# EV76C661_Sheet.net
KiCad netlist of a schematic drawn in Altium Designer
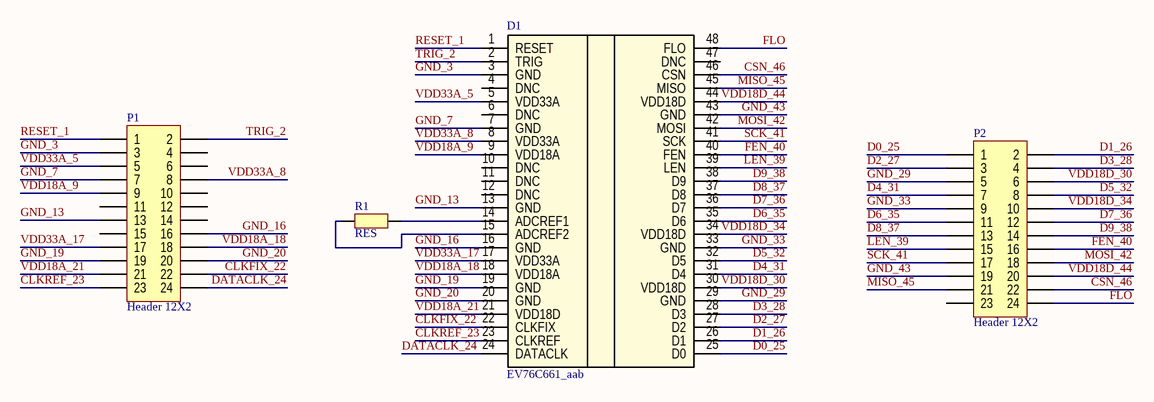
[diagram p0: EV76C661_Sheet.SchDoc]

(export (version "E")
  (design (tool "Eeschema 10.0.6"))
  (components
    (comp (ref "D1")
      (value "EV76C661_aab")
      (footprint "aab_Active:EV76C611_aab")
      (libsource (lib "aab_Schlib") (part "EV76C661_aab"))
    )
    (comp (ref "P1")
      (value "Header 12X2")
      (footprint "HDR2X12")
      (description "Header, 12-Pin, Dual row")
      (fields (field (name "PUBLISHER") "Altium Limited"))
      (libsource (lib "Miscellaneous Connectors") (part "Header 12X2"))
    )
    (comp (ref "P2")
      (value "Header 12X2")
      (footprint "HDR2X12")
      (description "Header, 12-Pin, Dual row")
      (fields (field (name "PUBLISHER") "Altium Limited"))
      (libsource (lib "Miscellaneous Connectors") (part "Header 12X2"))
    )
    (comp (ref "R1") (value "RES") (footprint "RES") (libsource (lib "aab_Schlib") (part "RES")))
  )
  (nets
    (net (code "1") (name "/CLKFIX_22") (class "Default")
      (node (ref "D1") (pin "22") (pinfunction "CLKFIX_22") (pintype "passive"))
      (node (ref "P1") (pin "22") (pinfunction "22_22") (pintype "passive"))
    )
    (net (code "2") (name "/CLKREF_23") (class "Default")
      (node (ref "D1") (pin "23") (pinfunction "CLKREF_23") (pintype "passive"))
      (node (ref "P1") (pin "23") (pinfunction "23_23") (pintype "passive"))
    )
    (net (code "3") (name "/CSN_46") (class "Default")
      (node (ref "D1") (pin "46") (pinfunction "CSN_46") (pintype "passive"))
      (node (ref "P2") (pin "22") (pinfunction "22_22") (pintype "passive"))
    )
    (net (code "4") (name "/D0_25") (class "Default")
      (node (ref "D1") (pin "25") (pinfunction "D0_25") (pintype "passive"))
      (node (ref "P2") (pin "1") (pinfunction "1_1") (pintype "passive"))
    )
    (net (code "5") (name "/D1_26") (class "Default")
      (node (ref "D1") (pin "26") (pinfunction "D1_26") (pintype "passive"))
      (node (ref "P2") (pin "2") (pinfunction "2_2") (pintype "passive"))
    )
    (net (code "6") (name "/D2_27") (class "Default")
      (node (ref "D1") (pin "27") (pinfunction "D2_27") (pintype "passive"))
      (node (ref "P2") (pin "3") (pinfunction "3_3") (pintype "passive"))
    )
    (net (code "7") (name "/D3_28") (class "Default")
      (node (ref "D1") (pin "28") (pinfunction "D3_28") (pintype "passive"))
      (node (ref "P2") (pin "4") (pinfunction "4_4") (pintype "passive"))
    )
    (net (code "8") (name "/D4_31") (class "Default")
      (node (ref "D1") (pin "31") (pinfunction "D4_31") (pintype "passive"))
      (node (ref "P2") (pin "7") (pinfunction "7_7") (pintype "passive"))
    )
    (net (code "9") (name "/D5_32") (class "Default")
      (node (ref "D1") (pin "32") (pinfunction "D5_32") (pintype "passive"))
      (node (ref "P2") (pin "8") (pinfunction "8_8") (pintype "passive"))
    )
    (net (code "10") (name "/D6_35") (class "Default")
      (node (ref "D1") (pin "35") (pinfunction "D6_35") (pintype "passive"))
      (node (ref "P2") (pin "11") (pinfunction "11_11") (pintype "passive"))
    )
    (net (code "11") (name "/D7_36") (class "Default")
      (node (ref "D1") (pin "36") (pinfunction "D7_36") (pintype "passive"))
      (node (ref "P2") (pin "12") (pinfunction "12_12") (pintype "passive"))
    )
    (net (code "12") (name "/D8_37") (class "Default")
      (node (ref "D1") (pin "37") (pinfunction "D8_37") (pintype "passive"))
      (node (ref "P2") (pin "13") (pinfunction "13_13") (pintype "passive"))
    )
    (net (code "13") (name "/D9_38") (class "Default")
      (node (ref "D1") (pin "38") (pinfunction "D9_38") (pintype "passive"))
      (node (ref "P2") (pin "14") (pinfunction "14_14") (pintype "passive"))
    )
    (net (code "14") (name "/DATACLK_24") (class "Default")
      (node (ref "D1") (pin "24") (pinfunction "DATACLK_24") (pintype "passive"))
      (node (ref "P1") (pin "24") (pinfunction "24_24") (pintype "passive"))
    )
    (net (code "15") (name "/FEN_40") (class "Default")
      (node (ref "D1") (pin "40") (pinfunction "FEN_40") (pintype "passive"))
      (node (ref "P2") (pin "16") (pinfunction "16_16") (pintype "passive"))
    )
    (net (code "16") (name "/FLO") (class "Default")
      (node (ref "D1") (pin "48") (pinfunction "FLO_48") (pintype "passive"))
      (node (ref "P2") (pin "24") (pinfunction "24_24") (pintype "passive"))
    )
    (net (code "17") (name "/GND_3") (class "Default")
      (node (ref "D1") (pin "3") (pinfunction "GND_3") (pintype "passive"))
      (node (ref "P1") (pin "3") (pinfunction "3_3") (pintype "passive"))
    )
    (net (code "18") (name "/GND_7") (class "Default")
      (node (ref "D1") (pin "7") (pinfunction "GND_7") (pintype "passive"))
      (node (ref "P1") (pin "7") (pinfunction "7_7") (pintype "passive"))
    )
    (net (code "19") (name "/GND_13") (class "Default")
      (node (ref "D1") (pin "13") (pinfunction "GND_13") (pintype "passive"))
      (node (ref "P1") (pin "13") (pinfunction "13_13") (pintype "passive"))
    )
    (net (code "20") (name "/GND_16") (class "Default")
      (node (ref "D1") (pin "16") (pinfunction "GND_16") (pintype "passive"))
      (node (ref "P1") (pin "16") (pinfunction "16_16") (pintype "passive"))
    )
    (net (code "21") (name "/GND_19") (class "Default")
      (node (ref "D1") (pin "19") (pinfunction "GND_19") (pintype "passive"))
      (node (ref "P1") (pin "19") (pinfunction "19_19") (pintype "passive"))
    )
    (net (code "22") (name "/GND_20") (class "Default")
      (node (ref "D1") (pin "20") (pinfunction "GND_20") (pintype "passive"))
      (node (ref "P1") (pin "20") (pinfunction "20_20") (pintype "passive"))
    )
    (net (code "23") (name "/GND_29") (class "Default")
      (node (ref "D1") (pin "29") (pinfunction "GND_29") (pintype "passive"))
      (node (ref "P2") (pin "5") (pinfunction "5_5") (pintype "passive"))
    )
    (net (code "24") (name "/GND_33") (class "Default")
      (node (ref "D1") (pin "33") (pinfunction "GND_33") (pintype "passive"))
      (node (ref "P2") (pin "9") (pinfunction "9_9") (pintype "passive"))
    )
    (net (code "25") (name "/GND_43") (class "Default")
      (node (ref "D1") (pin "43") (pinfunction "GND_43") (pintype "passive"))
      (node (ref "P2") (pin "19") (pinfunction "19_19") (pintype "passive"))
    )
    (net (code "26") (name "/LEN_39") (class "Default")
      (node (ref "D1") (pin "39") (pinfunction "LEN_39") (pintype "passive"))
      (node (ref "P2") (pin "15") (pinfunction "15_15") (pintype "passive"))
    )
    (net (code "27") (name "/MISO_45") (class "Default")
      (node (ref "D1") (pin "45") (pinfunction "MISO_45") (pintype "passive"))
      (node (ref "P2") (pin "21") (pinfunction "21_21") (pintype "passive"))
    )
    (net (code "28") (name "/MOSI_42") (class "Default")
      (node (ref "D1") (pin "42") (pinfunction "MOSI_42") (pintype "passive"))
      (node (ref "P2") (pin "18") (pinfunction "18_18") (pintype "passive"))
    )
    (net (code "29") (name "/RESET_1") (class "Default")
      (node (ref "D1") (pin "1") (pinfunction "RESET_1") (pintype "passive"))
      (node (ref "P1") (pin "1") (pinfunction "1_1") (pintype "passive"))
    )
    (net (code "30") (name "/SCK_41") (class "Default")
      (node (ref "D1") (pin "41") (pinfunction "SCK_41") (pintype "passive"))
      (node (ref "P2") (pin "17") (pinfunction "17_17") (pintype "passive"))
    )
    (net (code "31") (name "/TRIG_2") (class "Default")
      (node (ref "D1") (pin "2") (pinfunction "TRIG_2") (pintype "passive"))
      (node (ref "P1") (pin "2") (pinfunction "2_2") (pintype "passive"))
    )
    (net (code "32") (name "/VDD18A_9") (class "Default")
      (node (ref "D1") (pin "9") (pinfunction "VDD18A_9") (pintype "passive"))
      (node (ref "P1") (pin "9") (pinfunction "9_9") (pintype "passive"))
    )
    (net (code "33") (name "/VDD18A_18") (class "Default")
      (node (ref "D1") (pin "18") (pinfunction "VDD18A_18") (pintype "passive"))
      (node (ref "P1") (pin "18") (pinfunction "18_18") (pintype "passive"))
    )
    (net (code "34") (name "/VDD18A_21") (class "Default")
      (node (ref "D1") (pin "21") (pinfunction "VDD18D_21") (pintype "passive"))
      (node (ref "P1") (pin "21") (pinfunction "21_21") (pintype "passive"))
    )
    (net (code "35") (name "/VDD18D_30") (class "Default")
      (node (ref "D1") (pin "30") (pinfunction "VDD18D_30") (pintype "passive"))
      (node (ref "P2") (pin "6") (pinfunction "6_6") (pintype "passive"))
    )
    (net (code "36") (name "/VDD18D_34") (class "Default")
      (node (ref "D1") (pin "34") (pinfunction "VDD18D_34") (pintype "passive"))
      (node (ref "P2") (pin "10") (pinfunction "10_10") (pintype "passive"))
    )
    (net (code "37") (name "/VDD18D_44") (class "Default")
      (node (ref "D1") (pin "44") (pinfunction "VDD18D_44") (pintype "passive"))
      (node (ref "P2") (pin "20") (pinfunction "20_20") (pintype "passive"))
    )
    (net (code "38") (name "/VDD33A_5") (class "Default")
      (node (ref "D1") (pin "5") (pinfunction "VDD33A_5") (pintype "passive"))
      (node (ref "P1") (pin "5") (pinfunction "5_5") (pintype "passive"))
    )
    (net (code "39") (name "/VDD33A_8") (class "Default")
      (node (ref "D1") (pin "8") (pinfunction "VDD33A_8") (pintype "passive"))
      (node (ref "P1") (pin "8") (pinfunction "8_8") (pintype "passive"))
    )
    (net (code "40") (name "/VDD33A_17") (class "Default")
      (node (ref "D1") (pin "17") (pinfunction "VDD33A_17") (pintype "passive"))
      (node (ref "P1") (pin "17") (pinfunction "17_17") (pintype "passive"))
    )
    (net (code "41") (name "Net-(D1-ADCREF1)") (class "Default")
      (node (ref "D1") (pin "14") (pinfunction "ADCREF1_14") (pintype "passive"))
      (node (ref "R1") (pin "2") (pinfunction "2_2") (pintype "passive"))
    )
    (net (code "42") (name "Net-(D1-ADCREF2)") (class "Default")
      (node (ref "D1") (pin "15") (pinfunction "ADCREF2_15") (pintype "passive"))
      (node (ref "R1") (pin "1") (pinfunction "1_1") (pintype "passive"))
    )
    (net (code "43") (name "unconnected-(D1-DNC-Pad4)") (class "Default")
      (node (ref "D1") (pin "4") (pinfunction "DNC_4") (pintype "passive"))
    )
    (net (code "44") (name "unconnected-(D1-DNC-Pad6)") (class "Default")
      (node (ref "D1") (pin "6") (pinfunction "DNC_6") (pintype "passive"))
    )
    (net (code "45") (name "unconnected-(D1-DNC-Pad10)") (class "Default")
      (node (ref "D1") (pin "10") (pinfunction "DNC_10") (pintype "passive"))
    )
    (net (code "46") (name "unconnected-(D1-DNC-Pad11)") (class "Default")
      (node (ref "D1") (pin "11") (pinfunction "DNC_11") (pintype "passive"))
    )
    (net (code "47") (name "unconnected-(D1-DNC-Pad12)") (class "Default")
      (node (ref "D1") (pin "12") (pinfunction "DNC_12") (pintype "passive"))
    )
    (net (code "48") (name "unconnected-(D1-DNC-Pad47)") (class "Default")
      (node (ref "D1") (pin "47") (pinfunction "DNC_47") (pintype "passive"))
    )
    (net (code "49") (name "unconnected-(P1-Pad4)") (class "Default")
      (node (ref "P1") (pin "4") (pinfunction "4_4") (pintype "passive"))
    )
    (net (code "50") (name "unconnected-(P1-Pad6)") (class "Default")
      (node (ref "P1") (pin "6") (pinfunction "6_6") (pintype "passive"))
    )
    (net (code "51") (name "unconnected-(P1-Pad10)") (class "Default")
      (node (ref "P1") (pin "10") (pinfunction "10_10") (pintype "passive"))
    )
    (net (code "52") (name "unconnected-(P1-Pad11)") (class "Default")
      (node (ref "P1") (pin "11") (pinfunction "11_11") (pintype "passive"))
    )
    (net (code "53") (name "unconnected-(P1-Pad12)") (class "Default")
      (node (ref "P1") (pin "12") (pinfunction "12_12") (pintype "passive"))
    )
    (net (code "54") (name "unconnected-(P1-Pad14)") (class "Default")
      (node (ref "P1") (pin "14") (pinfunction "14_14") (pintype "passive"))
    )
    (net (code "55") (name "unconnected-(P1-Pad15)") (class "Default")
      (node (ref "P1") (pin "15") (pinfunction "15_15") (pintype "passive"))
    )
    (net (code "56") (name "unconnected-(P2-Pad23)") (class "Default")
      (node (ref "P2") (pin "23") (pinfunction "23_23") (pintype "passive"))
    )
  )
)
